# X-M3P1O5_led_V1_0.net
KiCad netlist of a schematic drawn in Altium Designer
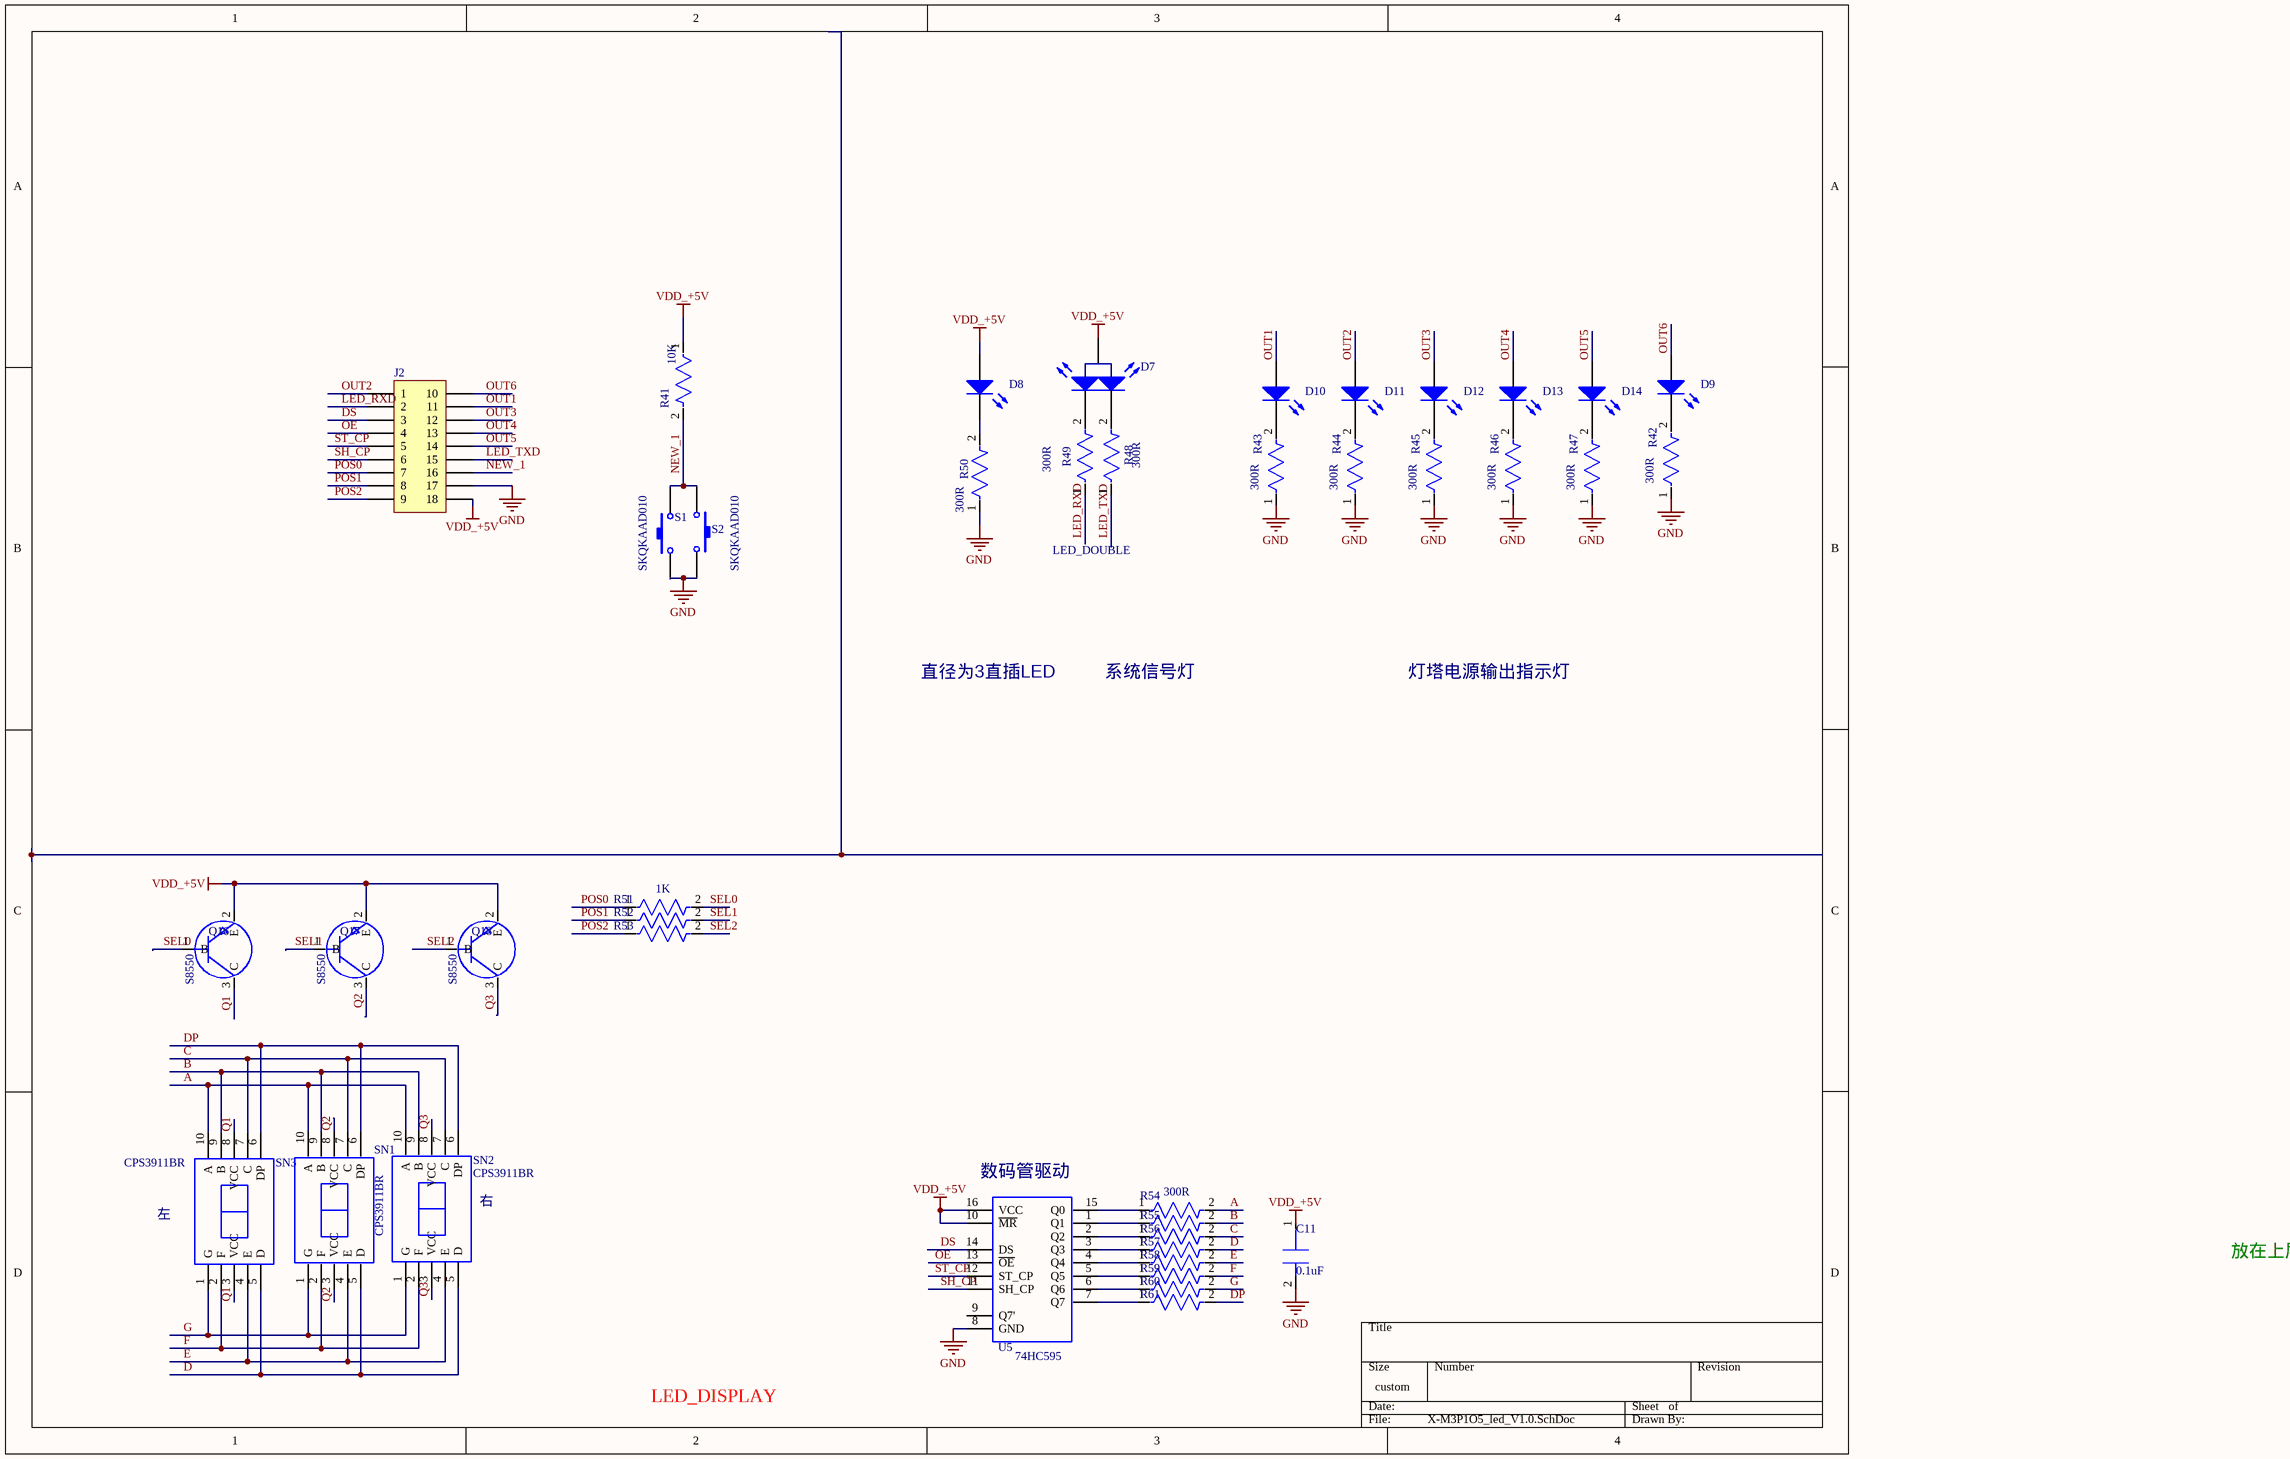
[diagram p0: X-M3P1O5_led_V1.0.SchDoc]

(export (version "E")
  (design (tool "Eeschema 10.0.6"))
  (components
    (comp (ref "C11")
      (value "0.1uF")
      (footprint "C0603")
      (description "SURFACE MOUNT CAPACITOR 0.031 X 0.061 INCHES")
      (fields (field (name "Comment") "100nF/50V"))
      (libsource (lib "*") (part "CAP0603"))
    )
    (comp (ref "D7")
      (value "LED_DOUBLE")
      (footprint "MODBUS_V1.0:LED-2.54-3/DOUBLE")
      (description "Typical INFRARED GaAs LED")
      (fields (field (name "PUBLISHER") "Altium Limited"))
      (libsource (lib "MODBUS") (part "LED_DOUBLE"))
    )
    (comp (ref "D8")
      (value "LED0")
      (footprint "MODBUS_V1.0:LED-2.54-3")
      (description "Typical INFRARED GaAs LED")
      (fields (field (name "PUBLISHER") "Altium Limited"))
      (libsource (lib "Miscellaneous Devices") (part "LED0"))
    )
    (comp (ref "D9")
      (value "LED0")
      (footprint "LED-2.54-3")
      (description "Typical INFRARED GaAs LED")
      (fields (field (name "PUBLISHER") "Altium Limited"))
      (libsource (lib "Miscellaneous Devices") (part "LED0"))
    )
    (comp (ref "D10")
      (value "LED0")
      (footprint "LED-2.54-3")
      (description "Typical INFRARED GaAs LED")
      (fields (field (name "PUBLISHER") "Altium Limited"))
      (libsource (lib "Miscellaneous Devices") (part "LED0"))
    )
    (comp (ref "D11")
      (value "LED0")
      (footprint "LED-2.54-3")
      (description "Typical INFRARED GaAs LED")
      (fields (field (name "PUBLISHER") "Altium Limited"))
      (libsource (lib "Miscellaneous Devices") (part "LED0"))
    )
    (comp (ref "D12")
      (value "LED0")
      (footprint "LED-2.54-3")
      (description "Typical INFRARED GaAs LED")
      (fields (field (name "PUBLISHER") "Altium Limited"))
      (libsource (lib "Miscellaneous Devices") (part "LED0"))
    )
    (comp (ref "D13")
      (value "LED0")
      (footprint "LED-2.54-3")
      (description "Typical INFRARED GaAs LED")
      (fields (field (name "PUBLISHER") "Altium Limited"))
      (libsource (lib "Miscellaneous Devices") (part "LED0"))
    )
    (comp (ref "D14")
      (value "LED0")
      (footprint "LED-2.54-3")
      (description "Typical INFRARED GaAs LED")
      (fields (field (name "PUBLISHER") "Altium Limited"))
      (libsource (lib "Miscellaneous Devices") (part "LED0"))
    )
    (comp (ref "J2")
      (value "Header 9X2A")
      (footprint "HDR2X9_CEN")
      (description "Header, 9-Pin, Dual row")
      (fields (field (name "PUBLISHER") "Altium Limited"))
      (libsource (lib "Miscellaneous Connectors") (part "Header 9X2A"))
    )
    (comp (ref "Q16")
      (value "S8550")
      (footprint "SOT-23")
      (description "QUAD AMPLIFIER SWITCHING PNP SILICON TRANSISTOR")
      (fields (field (name "PART NUMBER") "2N3906"))
      (libsource (lib "*") (part "PNP(SOT-23)"))
    )
    (comp (ref "Q17")
      (value "S8550")
      (footprint "SOT-23")
      (description "QUAD AMPLIFIER SWITCHING PNP SILICON TRANSISTOR")
      (fields (field (name "PART NUMBER") "2N3906"))
      (libsource (lib "*") (part "PNP(SOT-23)"))
    )
    (comp (ref "Q18")
      (value "S8550")
      (footprint "SOT-23")
      (description "QUAD AMPLIFIER SWITCHING PNP SILICON TRANSISTOR")
      (fields (field (name "PART NUMBER") "2N3906"))
      (libsource (lib "*") (part "PNP(SOT-23)"))
    )
    (comp (ref "R41")
      (value "10K")
      (footprint "R0603")
      (description "SURFACE MOUNT RESISTOR 0.031 X 0.061 INCHES, 1/10W")
      (libsource (lib "*") (part "RES0603"))
    )
    (comp (ref "R42")
      (value "300R")
      (footprint "R0603")
      (description "SURFACE MOUNT RESISTOR 0.031 X 0.061 INCHES, 1/10W")
      (fields (field (name "Comment") "20R"))
      (libsource (lib "*") (part "RES0603"))
    )
    (comp (ref "R43")
      (value "300R")
      (footprint "R0603")
      (description "SURFACE MOUNT RESISTOR 0.031 X 0.061 INCHES, 1/10W")
      (fields (field (name "Comment") "20R"))
      (libsource (lib "*") (part "RES0603"))
    )
    (comp (ref "R44")
      (value "300R")
      (footprint "R0603")
      (description "SURFACE MOUNT RESISTOR 0.031 X 0.061 INCHES, 1/10W")
      (fields (field (name "Comment") "20R"))
      (libsource (lib "*") (part "RES0603"))
    )
    (comp (ref "R45")
      (value "300R")
      (footprint "R0603")
      (description "SURFACE MOUNT RESISTOR 0.031 X 0.061 INCHES, 1/10W")
      (fields (field (name "Comment") "20R"))
      (libsource (lib "*") (part "RES0603"))
    )
    (comp (ref "R46")
      (value "300R")
      (footprint "R0603")
      (description "SURFACE MOUNT RESISTOR 0.031 X 0.061 INCHES, 1/10W")
      (fields (field (name "Comment") "20R"))
      (libsource (lib "*") (part "RES0603"))
    )
    (comp (ref "R47")
      (value "300R")
      (footprint "R0603")
      (description "SURFACE MOUNT RESISTOR 0.031 X 0.061 INCHES, 1/10W")
      (fields (field (name "Comment") "20R"))
      (libsource (lib "*") (part "RES0603"))
    )
    (comp (ref "R48")
      (value "300R")
      (footprint "MODBUS_V1.0:R0603")
      (description "SURFACE MOUNT RESISTOR 0.031 X 0.061 INCHES, 1/10W")
      (fields (field (name "Comment") "RES0603"))
      (libsource (lib "*") (part "RES0603"))
    )
    (comp (ref "R49")
      (value "300R")
      (footprint "MODBUS_V1.0:R0603")
      (description "SURFACE MOUNT RESISTOR 0.031 X 0.061 INCHES, 1/10W")
      (fields (field (name "Comment") "RES0603"))
      (libsource (lib "*") (part "RES0603"))
    )
    (comp (ref "R50")
      (value "300R")
      (footprint "MODBUS_V1.0:R0603")
      (description "SURFACE MOUNT RESISTOR 0.031 X 0.061 INCHES, 1/10W")
      (fields (field (name "Comment") "RES0603"))
      (libsource (lib "*") (part "RES0603"))
    )
    (comp (ref "R51")
      (value "1K")
      (footprint "R0603")
      (description "SURFACE MOUNT RESISTOR 0.031 X 0.061 INCHES, 1/10W")
      (libsource (lib "*") (part "RES0603"))
    )
    (comp (ref "R52")
      (value "1K")
      (footprint "R0603")
      (description "SURFACE MOUNT RESISTOR 0.031 X 0.061 INCHES, 1/10W")
      (libsource (lib "*") (part "RES0603"))
    )
    (comp (ref "R53")
      (value "1K")
      (footprint "R0603")
      (description "SURFACE MOUNT RESISTOR 0.031 X 0.061 INCHES, 1/10W")
      (libsource (lib "*") (part "RES0603"))
    )
    (comp (ref "R54")
      (value "300R")
      (footprint "R0603")
      (description "SURFACE MOUNT RESISTOR 0.031 X 0.061 INCHES, 1/10W")
      (fields (field (name "Comment") "300"))
      (libsource (lib "*") (part "RES0603"))
    )
    (comp (ref "R55")
      (value "300")
      (footprint "R0603")
      (description "SURFACE MOUNT RESISTOR 0.031 X 0.061 INCHES, 1/10W")
      (libsource (lib "*") (part "RES0603"))
    )
    (comp (ref "R56")
      (value "300")
      (footprint "R0603")
      (description "SURFACE MOUNT RESISTOR 0.031 X 0.061 INCHES, 1/10W")
      (libsource (lib "*") (part "RES0603"))
    )
    (comp (ref "R57")
      (value "300")
      (footprint "R0603")
      (description "SURFACE MOUNT RESISTOR 0.031 X 0.061 INCHES, 1/10W")
      (libsource (lib "*") (part "RES0603"))
    )
    (comp (ref "R58")
      (value "300")
      (footprint "R0603")
      (description "SURFACE MOUNT RESISTOR 0.031 X 0.061 INCHES, 1/10W")
      (libsource (lib "*") (part "RES0603"))
    )
    (comp (ref "R59")
      (value "300")
      (footprint "R0603")
      (description "SURFACE MOUNT RESISTOR 0.031 X 0.061 INCHES, 1/10W")
      (libsource (lib "*") (part "RES0603"))
    )
    (comp (ref "R60")
      (value "300")
      (footprint "R0603")
      (description "SURFACE MOUNT RESISTOR 0.031 X 0.061 INCHES, 1/10W")
      (libsource (lib "*") (part "RES0603"))
    )
    (comp (ref "R61")
      (value "300")
      (footprint "R0603")
      (description "SURFACE MOUNT RESISTOR 0.031 X 0.061 INCHES, 1/10W")
      (libsource (lib "*") (part "RES0603"))
    )
    (comp (ref "S1")
      (value "SKQKAAD010")
      (footprint "MODBUS_V1.0:SKQKAAD010")
      (description "Switch")
      (fields (field (name "PUBLISHER") "Altium Limited"))
      (libsource (lib "Miscellaneous Devices") (part "SW-PB"))
    )
    (comp (ref "S2")
      (value "SKQKAAD010")
      (footprint "MODBUS_V1.0:SKQKAAD010")
      (description "Switch")
      (fields (field (name "PUBLISHER") "Altium Limited"))
      (libsource (lib "Miscellaneous Devices") (part "SW-PB"))
    )
    (comp (ref "SN1")
      (value "CPS3911BR")
      (footprint "shumaguan_10.16*7.62")
      (libsource (lib "MODBUS_V1.0") (part "shumaguan13*10"))
    )
    (comp (ref "SN2")
      (value "CPS3911BR")
      (footprint "shumaguan_10.16*7.62")
      (libsource (lib "MODBUS_V1.0") (part "shumaguan13*10"))
    )
    (comp (ref "SN3")
      (value "CPS3911BR")
      (footprint "shumaguan_10.16*7.62")
      (libsource (lib "MODBUS_V1.0") (part "shumaguan13*10"))
    )
    (comp (ref "U5") (value "74HC595") (footprint "SO-1.27-16/4.0") (libsource (lib "*") (part "74HC595")))
  )
  (nets
    (net (code "1") (name "/A") (class "Default")
      (node (ref "R54") (pin "2") (pintype "passive"))
      (node (ref "SN1") (pin "10") (pinfunction "A_10") (pintype "passive"))
      (node (ref "SN2") (pin "10") (pinfunction "A_10") (pintype "passive"))
      (node (ref "SN3") (pin "10") (pinfunction "A_10") (pintype "passive"))
    )
    (net (code "2") (name "/B") (class "Default")
      (node (ref "R55") (pin "2") (pintype "passive"))
      (node (ref "SN1") (pin "9") (pinfunction "B_9") (pintype "passive"))
      (node (ref "SN2") (pin "9") (pinfunction "B_9") (pintype "passive"))
      (node (ref "SN3") (pin "9") (pinfunction "B_9") (pintype "passive"))
    )
    (net (code "3") (name "/C") (class "Default")
      (node (ref "R56") (pin "2") (pintype "passive"))
      (node (ref "SN1") (pin "7") (pinfunction "C_7") (pintype "passive"))
      (node (ref "SN2") (pin "7") (pinfunction "C_7") (pintype "passive"))
      (node (ref "SN3") (pin "7") (pinfunction "C_7") (pintype "passive"))
    )
    (net (code "4") (name "/D") (class "Default")
      (node (ref "R57") (pin "2") (pintype "passive"))
      (node (ref "SN1") (pin "5") (pinfunction "D_5") (pintype "passive"))
      (node (ref "SN2") (pin "5") (pinfunction "D_5") (pintype "passive"))
      (node (ref "SN3") (pin "5") (pinfunction "D_5") (pintype "passive"))
    )
    (net (code "5") (name "/DP") (class "Default")
      (node (ref "R61") (pin "2") (pintype "passive"))
      (node (ref "SN1") (pin "6") (pinfunction "DP_6") (pintype "passive"))
      (node (ref "SN2") (pin "6") (pinfunction "DP_6") (pintype "passive"))
      (node (ref "SN3") (pin "6") (pinfunction "DP_6") (pintype "passive"))
    )
    (net (code "6") (name "/DS") (class "Default")
      (node (ref "J2") (pin "3") (pinfunction "3_3") (pintype "passive"))
      (node (ref "U5") (pin "14") (pinfunction "DS_14") (pintype "passive"))
    )
    (net (code "7") (name "/E") (class "Default")
      (node (ref "R58") (pin "2") (pintype "passive"))
      (node (ref "SN1") (pin "4") (pinfunction "E_4") (pintype "passive"))
      (node (ref "SN2") (pin "4") (pinfunction "E_4") (pintype "passive"))
      (node (ref "SN3") (pin "4") (pinfunction "E_4") (pintype "passive"))
    )
    (net (code "8") (name "/F") (class "Default")
      (node (ref "R59") (pin "2") (pintype "passive"))
      (node (ref "SN1") (pin "2") (pinfunction "F_2") (pintype "passive"))
      (node (ref "SN2") (pin "2") (pinfunction "F_2") (pintype "passive"))
      (node (ref "SN3") (pin "2") (pinfunction "F_2") (pintype "passive"))
    )
    (net (code "9") (name "/G") (class "Default")
      (node (ref "R60") (pin "2") (pintype "passive"))
      (node (ref "SN1") (pin "1") (pinfunction "G_1") (pintype "passive"))
      (node (ref "SN2") (pin "1") (pinfunction "G_1") (pintype "passive"))
      (node (ref "SN3") (pin "1") (pinfunction "G_1") (pintype "passive"))
    )
    (net (code "10") (name "/LED_RXD") (class "Default")
      (node (ref "J2") (pin "2") (pinfunction "2_2") (pintype "passive"))
      (node (ref "R49") (pin "1") (pintype "passive"))
    )
    (net (code "11") (name "/LED_TXD") (class "Default")
      (node (ref "J2") (pin "15") (pinfunction "15_15") (pintype "passive"))
      (node (ref "R48") (pin "1") (pintype "passive"))
    )
    (net (code "12") (name "/NEW_1") (class "Default")
      (node (ref "J2") (pin "16") (pinfunction "16_16") (pintype "passive"))
      (node (ref "R41") (pin "2") (pintype "passive"))
      (node (ref "S1") (pin "2") (pinfunction "2_2") (pintype "passive"))
      (node (ref "S2") (pin "1") (pinfunction "1_1") (pintype "passive"))
    )
    (net (code "13") (name "/OE") (class "Default")
      (node (ref "J2") (pin "4") (pinfunction "4_4") (pintype "passive"))
      (node (ref "U5") (pin "13") (pinfunction "OE_13") (pintype "passive"))
    )
    (net (code "14") (name "/OUT1") (class "Default")
      (node (ref "D10") (pin "1") (pinfunction "A_1") (pintype "passive"))
      (node (ref "J2") (pin "11") (pinfunction "11_11") (pintype "passive"))
    )
    (net (code "15") (name "/OUT2") (class "Default")
      (node (ref "D11") (pin "1") (pinfunction "A_1") (pintype "passive"))
      (node (ref "J2") (pin "1") (pinfunction "1_1") (pintype "passive"))
    )
    (net (code "16") (name "/OUT3") (class "Default")
      (node (ref "D12") (pin "1") (pinfunction "A_1") (pintype "passive"))
      (node (ref "J2") (pin "12") (pinfunction "12_12") (pintype "passive"))
    )
    (net (code "17") (name "/OUT4") (class "Default")
      (node (ref "D13") (pin "1") (pinfunction "A_1") (pintype "passive"))
      (node (ref "J2") (pin "13") (pinfunction "13_13") (pintype "passive"))
    )
    (net (code "18") (name "/OUT5") (class "Default")
      (node (ref "D14") (pin "1") (pinfunction "A_1") (pintype "passive"))
      (node (ref "J2") (pin "14") (pinfunction "14_14") (pintype "passive"))
    )
    (net (code "19") (name "/OUT6") (class "Default")
      (node (ref "D9") (pin "1") (pinfunction "A_1") (pintype "passive"))
      (node (ref "J2") (pin "10") (pinfunction "10_10") (pintype "passive"))
    )
    (net (code "20") (name "/POS0") (class "Default")
      (node (ref "J2") (pin "7") (pinfunction "7_7") (pintype "passive"))
      (node (ref "R51") (pin "1") (pintype "passive"))
    )
    (net (code "21") (name "/POS1") (class "Default")
      (node (ref "J2") (pin "8") (pinfunction "8_8") (pintype "passive"))
      (node (ref "R52") (pin "1") (pintype "passive"))
    )
    (net (code "22") (name "/POS2") (class "Default")
      (node (ref "J2") (pin "9") (pinfunction "9_9") (pintype "passive"))
      (node (ref "R53") (pin "1") (pintype "passive"))
    )
    (net (code "23") (name "/Q1") (class "Default")
      (node (ref "Q16") (pin "3") (pinfunction "C_3") (pintype "passive"))
      (node (ref "SN3") (pin "3") (pinfunction "VCC_3") (pintype "passive"))
      (node (ref "SN3") (pin "8") (pinfunction "VCC_8") (pintype "passive"))
    )
    (net (code "24") (name "/Q2") (class "Default")
      (node (ref "Q17") (pin "3") (pinfunction "C_3") (pintype "passive"))
      (node (ref "SN1") (pin "3") (pinfunction "VCC_3") (pintype "passive"))
      (node (ref "SN1") (pin "8") (pinfunction "VCC_8") (pintype "passive"))
    )
    (net (code "25") (name "/Q3") (class "Default")
      (node (ref "Q18") (pin "3") (pinfunction "C_3") (pintype "passive"))
      (node (ref "SN2") (pin "3") (pinfunction "VCC_3") (pintype "passive"))
      (node (ref "SN2") (pin "8") (pinfunction "VCC_8") (pintype "passive"))
    )
    (net (code "26") (name "/SEL0") (class "Default")
      (node (ref "Q16") (pin "1") (pinfunction "B_1") (pintype "passive"))
      (node (ref "R51") (pin "2") (pintype "passive"))
    )
    (net (code "27") (name "/SEL1") (class "Default")
      (node (ref "Q17") (pin "1") (pinfunction "B_1") (pintype "passive"))
      (node (ref "R52") (pin "2") (pintype "passive"))
    )
    (net (code "28") (name "/SEL2") (class "Default")
      (node (ref "Q18") (pin "1") (pinfunction "B_1") (pintype "passive"))
      (node (ref "R53") (pin "2") (pintype "passive"))
    )
    (net (code "29") (name "/SH_CP") (class "Default")
      (node (ref "J2") (pin "6") (pinfunction "6_6") (pintype "passive"))
      (node (ref "U5") (pin "11") (pinfunction "SH_CP_11") (pintype "passive"))
    )
    (net (code "30") (name "/ST_CP") (class "Default")
      (node (ref "J2") (pin "5") (pinfunction "5_5") (pintype "passive"))
      (node (ref "U5") (pin "12") (pinfunction "ST_CP_12") (pintype "passive"))
    )
    (net (code "31") (name "GND") (class "Default")
      (node (ref "C11") (pin "2") (pintype "passive"))
      (node (ref "J2") (pin "17") (pinfunction "17_17") (pintype "passive"))
      (node (ref "R42") (pin "1") (pintype "passive"))
      (node (ref "R43") (pin "1") (pintype "passive"))
      (node (ref "R44") (pin "1") (pintype "passive"))
      (node (ref "R45") (pin "1") (pintype "passive"))
      (node (ref "R46") (pin "1") (pintype "passive"))
      (node (ref "R47") (pin "1") (pintype "passive"))
      (node (ref "R50") (pin "1") (pintype "passive"))
      (node (ref "S1") (pin "1") (pinfunction "1_1") (pintype "passive"))
      (node (ref "S2") (pin "2") (pinfunction "2_2") (pintype "passive"))
      (node (ref "U5") (pin "8") (pinfunction "GND_8") (pintype "passive"))
    )
    (net (code "32") (name "Net-(D7-A-Pad1)") (class "Default")
      (node (ref "D7") (pin "1") (pinfunction "A_1") (pintype "passive"))
      (node (ref "R49") (pin "2") (pintype "passive"))
    )
    (net (code "33") (name "Net-(D7-A-Pad3)") (class "Default")
      (node (ref "D7") (pin "3") (pinfunction "A_3") (pintype "passive"))
      (node (ref "R48") (pin "2") (pintype "passive"))
    )
    (net (code "34") (name "Net-(D8-K)") (class "Default")
      (node (ref "D8") (pin "2") (pinfunction "K_2") (pintype "passive"))
      (node (ref "R50") (pin "2") (pintype "passive"))
    )
    (net (code "35") (name "Net-(D9-K)") (class "Default")
      (node (ref "D9") (pin "2") (pinfunction "K_2") (pintype "passive"))
      (node (ref "R42") (pin "2") (pintype "passive"))
    )
    (net (code "36") (name "Net-(D10-K)") (class "Default")
      (node (ref "D10") (pin "2") (pinfunction "K_2") (pintype "passive"))
      (node (ref "R43") (pin "2") (pintype "passive"))
    )
    (net (code "37") (name "Net-(D11-K)") (class "Default")
      (node (ref "D11") (pin "2") (pinfunction "K_2") (pintype "passive"))
      (node (ref "R44") (pin "2") (pintype "passive"))
    )
    (net (code "38") (name "Net-(D12-K)") (class "Default")
      (node (ref "D12") (pin "2") (pinfunction "K_2") (pintype "passive"))
      (node (ref "R45") (pin "2") (pintype "passive"))
    )
    (net (code "39") (name "Net-(D13-K)") (class "Default")
      (node (ref "D13") (pin "2") (pinfunction "K_2") (pintype "passive"))
      (node (ref "R46") (pin "2") (pintype "passive"))
    )
    (net (code "40") (name "Net-(D14-K)") (class "Default")
      (node (ref "D14") (pin "2") (pinfunction "K_2") (pintype "passive"))
      (node (ref "R47") (pin "2") (pintype "passive"))
    )
    (net (code "41") (name "Net-(U5-Q0)") (class "Default")
      (node (ref "R54") (pin "1") (pintype "passive"))
      (node (ref "U5") (pin "15") (pinfunction "Q0_15") (pintype "passive"))
    )
    (net (code "42") (name "Net-(U5-Q1)") (class "Default")
      (node (ref "R55") (pin "1") (pintype "passive"))
      (node (ref "U5") (pin "1") (pinfunction "Q1_1") (pintype "passive"))
    )
    (net (code "43") (name "Net-(U5-Q2)") (class "Default")
      (node (ref "R56") (pin "1") (pintype "passive"))
      (node (ref "U5") (pin "2") (pinfunction "Q2_2") (pintype "passive"))
    )
    (net (code "44") (name "Net-(U5-Q3)") (class "Default")
      (node (ref "R57") (pin "1") (pintype "passive"))
      (node (ref "U5") (pin "3") (pinfunction "Q3_3") (pintype "passive"))
    )
    (net (code "45") (name "Net-(U5-Q4)") (class "Default")
      (node (ref "R58") (pin "1") (pintype "passive"))
      (node (ref "U5") (pin "4") (pinfunction "Q4_4") (pintype "passive"))
    )
    (net (code "46") (name "Net-(U5-Q5)") (class "Default")
      (node (ref "R59") (pin "1") (pintype "passive"))
      (node (ref "U5") (pin "5") (pinfunction "Q5_5") (pintype "passive"))
    )
    (net (code "47") (name "Net-(U5-Q6)") (class "Default")
      (node (ref "R60") (pin "1") (pintype "passive"))
      (node (ref "U5") (pin "6") (pinfunction "Q6_6") (pintype "passive"))
    )
    (net (code "48") (name "Net-(U5-Q7)") (class "Default")
      (node (ref "R61") (pin "1") (pintype "passive"))
      (node (ref "U5") (pin "7") (pinfunction "Q7_7") (pintype "passive"))
    )
    (net (code "49") (name "VDD_+5V") (class "Default")
      (node (ref "C11") (pin "1") (pintype "passive"))
      (node (ref "D7") (pin "2") (pinfunction "K_2") (pintype "passive"))
      (node (ref "D8") (pin "1") (pinfunction "A_1") (pintype "passive"))
      (node (ref "J2") (pin "18") (pinfunction "18_18") (pintype "passive"))
      (node (ref "Q16") (pin "2") (pinfunction "E_2") (pintype "passive"))
      (node (ref "Q17") (pin "2") (pinfunction "E_2") (pintype "passive"))
      (node (ref "Q18") (pin "2") (pinfunction "E_2") (pintype "passive"))
      (node (ref "R41") (pin "1") (pintype "passive"))
      (node (ref "U5") (pin "10") (pinfunction "MR_10") (pintype "passive"))
      (node (ref "U5") (pin "16") (pinfunction "VCC_16") (pintype "passive"))
    )
    (net (code "50") (name "unconnected-(U5-Q7'-Pad9)") (class "Default")
      (node (ref "U5") (pin "9") (pinfunction "Q7'_9") (pintype "passive"))
    )
  )
)
